# Controller_Board_-_Microcontroller.net
KiCad netlist of a schematic drawn in Altium Designer
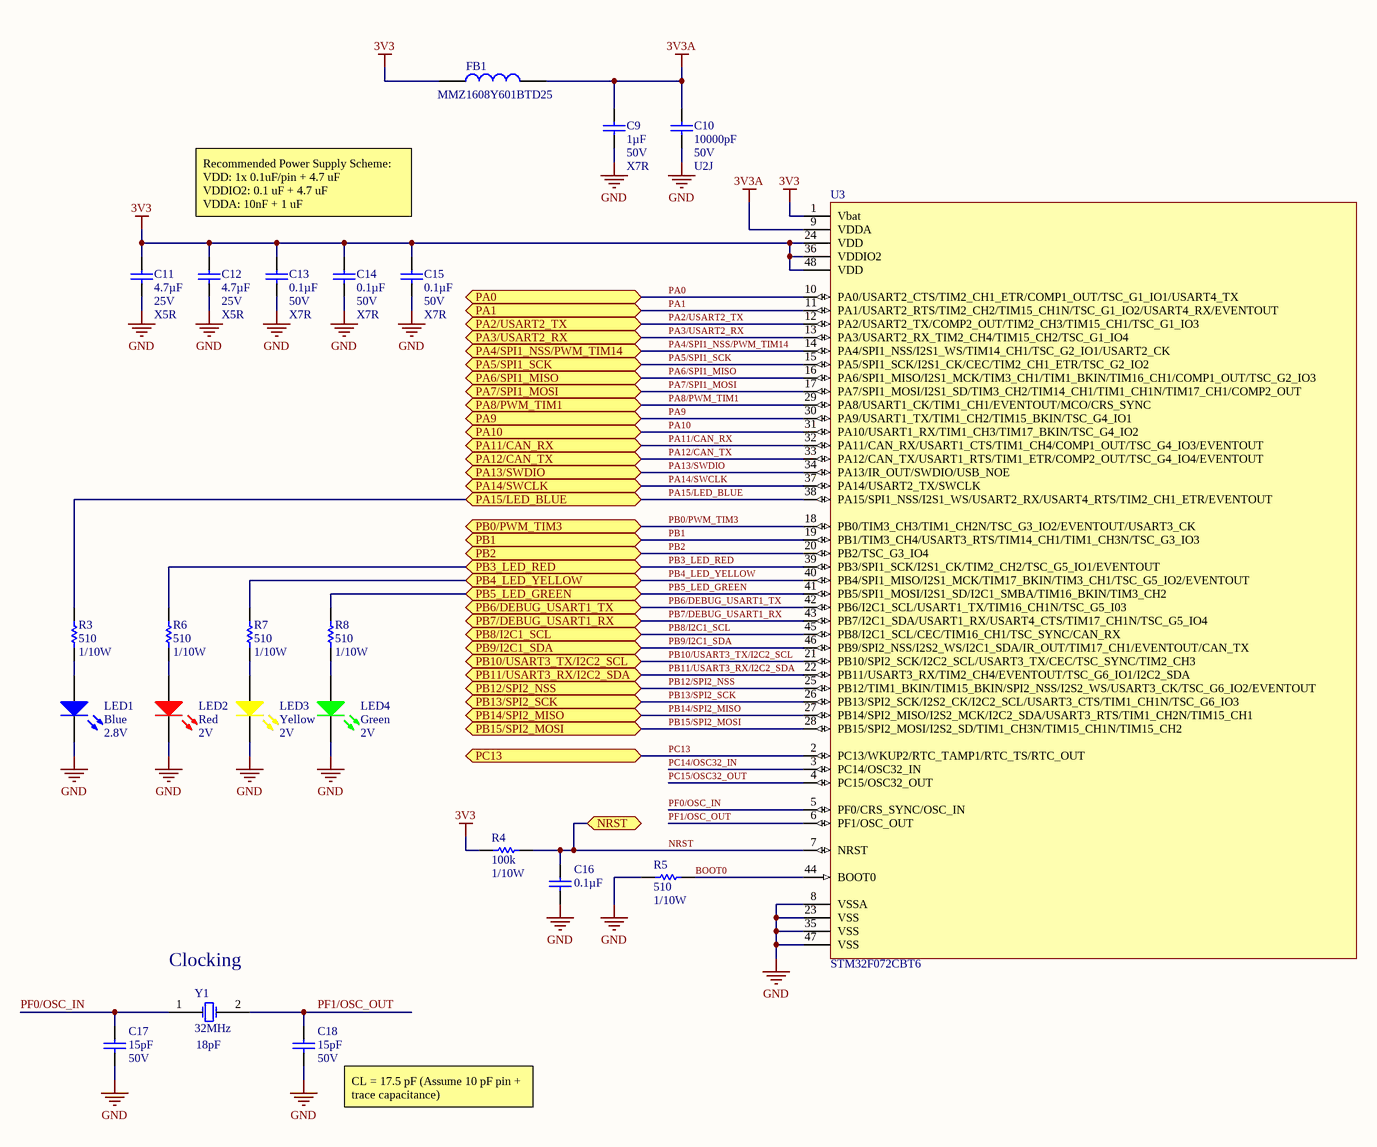
[diagram p0: Controller Board - Microcontroller.SchDoc]

(export (version "E")
  (design (tool "Eeschema 10.0.6"))
  (components
    (comp (ref "C9")
      (value "CAP CER 1UF 50V 10% X7R 0603")
      (footprint "CAP, 0603")
      (description "1µF ±10% 50V Ceramic Capacitor X7R 0603 (1608 Metric)")
      (fields
        (field (name "TOLERANCE") "±10%")
        (field (name "CAPACITANCE") "1µF")
        (field (name "VOLTAGE") "50V")
        (field (name "TEMPERATURE COEFFICIENT") "X7R")
      )
      (libsource (lib "Schematic Diagrams") (part "CAP CER 1UF 50V 10% X7R 0603"))
    )
    (comp (ref "C10")
      (value "CAP CER 10nF 50V 5% X7R 0603")
      (footprint "CAP, 0603")
      (description "10000pF ±5% 50V Ceramic Capacitor U2J 0603 (1608 Metric)")
      (fields
        (field (name "TOLERANCE") "±5%")
        (field (name "CAPACITANCE") "10000pF")
        (field (name "VOLTAGE") "50V")
        (field (name "TEMPERATURE COEFFICIENT") "U2J")
      )
      (libsource (lib "Schematic Diagrams") (part "CAP CER 10nF 50V 5% X7R 0603"))
    )
    (comp (ref "C11")
      (value "CAP CER 4.7UF 25V 10% X5R 0603")
      (footprint "CAP, 0603")
      (description "4.7µF ±10% 25V Ceramic Capacitor X5R 0603 (1608 Metric)")
      (fields
        (field (name "TOLERANCE") "±10%")
        (field (name "CAPACITANCE") "4.7µF")
        (field (name "VOLTAGE") "25V")
        (field (name "TEMPERATURE COEFFICIENT") "X5R")
      )
      (libsource (lib "Schematic Diagrams") (part "CAP CER 4.7UF 25V 10% X5R 0603"))
    )
    (comp (ref "C12")
      (value "CAP CER 4.7UF 25V 10% X5R 0603")
      (footprint "CAP, 0603")
      (description "4.7µF ±10% 25V Ceramic Capacitor X5R 0603 (1608 Metric)")
      (fields
        (field (name "TOLERANCE") "±10%")
        (field (name "CAPACITANCE") "4.7µF")
        (field (name "VOLTAGE") "25V")
        (field (name "TEMPERATURE COEFFICIENT") "X5R")
      )
      (libsource (lib "Schematic Diagrams") (part "CAP CER 4.7UF 25V 10% X5R 0603"))
    )
    (comp (ref "C13")
      (value "CAP CER 0.1UF 50V 10% X7R 0603")
      (footprint "CAP, 0603")
      (description "0.10µF ±10% 50V Ceramic Capacitor X7R 0603 (1608 Metric)")
      (fields
        (field (name "TOLERANCE") "±10%")
        (field (name "CAPACITANCE") "0.1µF")
        (field (name "VOLTAGE") "50V")
        (field (name "TEMPERATURE COEFFICIENT") "X7R")
      )
      (libsource (lib "Schematic Diagrams") (part "CAP CER 0.1UF 50V 10% X7R 0603"))
    )
    (comp (ref "C14")
      (value "CAP CER 0.1UF 50V 10% X7R 0603")
      (footprint "CAP, 0603")
      (description "0.10µF ±10% 50V Ceramic Capacitor X7R 0603 (1608 Metric)")
      (fields
        (field (name "TOLERANCE") "±10%")
        (field (name "CAPACITANCE") "0.1µF")
        (field (name "VOLTAGE") "50V")
        (field (name "TEMPERATURE COEFFICIENT") "X7R")
      )
      (libsource (lib "Schematic Diagrams") (part "CAP CER 0.1UF 50V 10% X7R 0603"))
    )
    (comp (ref "C15")
      (value "CAP CER 0.1UF 50V 10% X7R 0603")
      (footprint "CAP, 0603")
      (description "0.10µF ±10% 50V Ceramic Capacitor X7R 0603 (1608 Metric)")
      (fields
        (field (name "TOLERANCE") "±10%")
        (field (name "CAPACITANCE") "0.1µF")
        (field (name "VOLTAGE") "50V")
        (field (name "TEMPERATURE COEFFICIENT") "X7R")
      )
      (libsource (lib "Schematic Diagrams") (part "CAP CER 0.1UF 50V 10% X7R 0603"))
    )
    (comp (ref "C16")
      (value "CAP CER 0.1UF 50V 10% X7R 0603")
      (footprint "CAP, 0603")
      (description "0.10µF ±10% 50V Ceramic Capacitor X7R 0603 (1608 Metric)")
      (fields
        (field (name "VOLTAGE") "50V")
        (field (name "TOLERANCE") "±10%")
        (field (name "CAPACITANCE") "0.1µF")
      )
      (libsource (lib "Schematic Diagrams") (part "CAP CER 0.1UF 50V 10% X7R 0603"))
    )
    (comp (ref "C17")
      (value "CAP CER 15PF 50V ±5% NPO 0603")
      (footprint "CAP, 0603")
      (description "15pF ±5% 50V Ceramic Capacitor C0G, NP0 0603 (1608 Metric)")
      (fields
        (field (name "VOLTAGE") "50V")
        (field (name "TOLERANCE") "±5%")
        (field (name "CAPACITANCE") "15pF")
      )
      (libsource (lib "Schematic Diagrams") (part "CAP CER 15PF 50V ±5% NPO 0603"))
    )
    (comp (ref "C18")
      (value "CAP CER 15PF 50V ±5% NPO 0603")
      (footprint "CAP, 0603")
      (description "15pF ±5% 50V Ceramic Capacitor C0G, NP0 0603 (1608 Metric)")
      (fields
        (field (name "VOLTAGE") "50V")
        (field (name "TOLERANCE") "±5%")
        (field (name "CAPACITANCE") "15pF")
      )
      (libsource (lib "Schematic Diagrams") (part "CAP CER 15PF 50V ±5% NPO 0603"))
    )
    (comp (ref "FB1")
      (value "FB 600 OHM 1LN 0603")
      (footprint "FB 0603")
      (description "FERRITE BEAD 600 OHM 0603 1LN")
      (fields
        (field (name "MANUFACTURER") "TDK")
        (field (name "TOLERANCE") "25%")
        (field (name "MANUFACTURER PART NUMBER") "MMZ1608Y601BTD25")
      )
      (libsource (lib "Schematic Diagrams") (part "FB 600 OHM 1LN 0603"))
    )
    (comp (ref "LED1")
      (value "LED BLUE CLEAR 2.8V 0603")
      (footprint "LED_0603")
      (description "Blue 470nm LED Indication - Discrete 2.8V 0603 (1608 Metric)")
      (fields (field (name "COLOR") "Blue") (field (name "VOLTAGE - FORWARD (VF) (TYP)") "2.8V"))
      (libsource (lib "Schematic Diagrams") (part "LED BLUE CLEAR 2.8V 0603"))
    )
    (comp (ref "LED2")
      (value "LED RED CLEAR 2V 0603")
      (footprint "LED_0603")
      (description "Red 631nm LED Indication - Discrete 2V 0603 (1608 Metric)")
      (fields
        (field (name "MANUFACTURER") "Wurth Electronics Inc.")
        (field (name "MANUFACTURER PART NUMBER") "150060RS75000")
        (field (name "COLOR") "Red")
        (field (name "VOLTAGE - FORWARD (VF) (TYP)") "2V")
      )
      (libsource (lib "Schematic Diagrams") (part "LED RED CLEAR 2V 0603"))
    )
    (comp (ref "LED3")
      (value "LED YELLOW CLEAR 2.1V 0603")
      (footprint "LED_0603")
      (description "Yellow 590nm LED Indication - Discrete 2V 0603 (1608 Metric)")
      (fields
        (field (name "MANUFACTURER") "Wurth Electronics Inc.")
        (field (name "MANUFACTURER PART NUMBER") "150060YS75000")
        (field (name "COLOR") "Yellow")
        (field (name "VOLTAGE - FORWARD (VF) (TYP)") "2V")
      )
      (libsource (lib "Schematic Diagrams") (part "LED YELLOW CLEAR 2.1V 0603"))
    )
    (comp (ref "LED4")
      (value "LED GREEN CLEAR 2V 0603")
      (footprint "LED_0603")
      (description "Green 572nm LED Indication - Discrete 2V 0603 (1608 Metric)")
      (fields
        (field (name "MANUFACTURER") "Wurth Electronics Inc.")
        (field (name "MANUFACTURER PART NUMBER") "150060VS75000")
        (field (name "COLOR") "Green")
        (field (name "VOLTAGE - FORWARD (VF) (TYP)") "2V")
      )
      (libsource (lib "Schematic Diagrams") (part "LED GREEN CLEAR 2V 0603"))
    )
    (comp (ref "R3")
      (value "RES 510 OHM 5% 1/10W 0603")
      (footprint "RES, 0603")
      (description "RES SMD 510 OHM 5% 1/10W 0603")
      (fields
        (field (name "TOLERANCE") "±5%")
        (field (name "RESISTANCE") "510")
        (field (name "POWER") "1/10W")
      )
      (libsource (lib "altium-import") (part "root_0_RES 510 OHM 5% 1/10W 0603_"))
    )
    (comp (ref "R4")
      (value "RES 100K OHM 5% 1/8W 0603")
      (footprint "RES, 0603")
      (description "RES SMD 100K OHM 5% 1/10W 0603")
      (fields
        (field (name "TOLERANCE") "±5%")
        (field (name "RESISTANCE") "100k")
        (field (name "POWER") "1/10W")
      )
      (libsource (lib "Schematic Diagrams") (part "RES 100K OHM 5% 1/8W 0603"))
    )
    (comp (ref "R5")
      (value "RES 510 OHM 5% 1/10W 0603")
      (footprint "RES, 0603")
      (description "RES SMD 510 OHM 5% 1/10W 0603")
      (fields
        (field (name "TOLERANCE") "±5%")
        (field (name "RESISTANCE") "510")
        (field (name "POWER") "1/10W")
      )
      (libsource (lib "Schematic Diagrams") (part "RES 510 OHM 5% 1/10W 0603"))
    )
    (comp (ref "R6")
      (value "RES 510 OHM 5% 1/10W 0603")
      (footprint "RES, 0603")
      (description "RES SMD 510 OHM 5% 1/10W 0603")
      (fields
        (field (name "TOLERANCE") "±5%")
        (field (name "RESISTANCE") "510")
        (field (name "POWER") "1/10W")
      )
      (libsource (lib "altium-import") (part "root_0_RES 510 OHM 5% 1/10W 0603_"))
    )
    (comp (ref "R7")
      (value "RES 510 OHM 5% 1/10W 0603")
      (footprint "RES, 0603")
      (description "RES SMD 510 OHM 5% 1/10W 0603")
      (fields
        (field (name "TOLERANCE") "±5%")
        (field (name "RESISTANCE") "510")
        (field (name "POWER") "1/10W")
      )
      (libsource (lib "altium-import") (part "root_0_RES 510 OHM 5% 1/10W 0603_"))
    )
    (comp (ref "R8")
      (value "RES 510 OHM 5% 1/10W 0603")
      (footprint "RES, 0603")
      (description "RES SMD 510 OHM 5% 1/10W 0603")
      (fields
        (field (name "TOLERANCE") "±5%")
        (field (name "RESISTANCE") "510")
        (field (name "POWER") "1/10W")
      )
      (libsource (lib "altium-import") (part "root_0_RES 510 OHM 5% 1/10W 0603_"))
    )
    (comp (ref "U3")
      (value "IC MCU 32BIT 128KB FLASH 48LQFP")
      (footprint "TSQFP50P890X890X160-48M")
      (description "ARM® Cortex®-M0 STM32 F0 Microcontroller IC 32-Bit 48MHz 128KB (128K x 8) FLASH 48-LQFP (7x7)")
      (fields (field (name "MANUFACTURER PART NUMBER 1") "STM32F072CBT6"))
      (libsource (lib "Schematic Diagrams") (part "IC MCU 32BIT 128KB FLASH 48LQFP"))
    )
    (comp (ref "Y1")
      (value "CRYSTAL 32 MHz 18PF 2-SMD")
      (footprint "CRYSTAL ABM7")
      (description "32MHz ±20ppm Crystal 18pF 50 Ohms 2-SMD, No Lead")
      (fields
        (field (name "MANUFACTURER") "Abracon")
        (field (name "LOAD CAPACITANCE") "18pF")
        (field (name "TOLERANCE") "20ppm")
        (field (name "FREQUENCY") "32MHz")
      )
      (libsource (lib "Schematic Diagrams") (part "CRYSTAL 32 MHz 18PF 2-SMD"))
    )
  )
  (nets
    (net (code "1") (name "/BOOT0") (class "Default")
      (node (ref "R5") (pin "2") (pinfunction "2_2") (pintype "passive"))
      (node (ref "U3") (pin "44") (pinfunction "BOOT0_44") (pintype "input"))
    )
    (net (code "2") (name "/NRST") (class "Default")
      (node (ref "C16") (pin "2") (pinfunction "2_2") (pintype "passive"))
      (node (ref "R4") (pin "1") (pinfunction "1_1") (pintype "passive"))
      (node (ref "U3") (pin "7") (pinfunction "NRST_7") (pintype "bidirectional"))
    )
    (net (code "3") (name "/PA0") (class "Default")
      (node (ref "U3") (pin "10") (pinfunction "PA0/USART2_CTS/TIM2_CH1_ETR/COMP1_OUT/TSC_G1_IO1/USART4_TX_10") (pintype "bidirectional"))
    )
    (net (code "4") (name "/PA1") (class "Default")
      (node (ref "U3") (pin "11") (pinfunction "PA1/USART2_RTS/TIM2_CH2/TIM15_CH1N/TSC_G1_IO2/USART4_RX/EVENTOUT_11") (pintype "bidirectional"))
    )
    (net (code "5") (name "/PA2{slash}USART2_TX") (class "Default")
      (node (ref "U3") (pin "12") (pinfunction "PA2/USART2_TX/COMP2_OUT/TIM2_CH3/TIM15_CH1/TSC_G1_IO3_12") (pintype "bidirectional"))
    )
    (net (code "6") (name "/PA3{slash}USART2_RX") (class "Default")
      (node (ref "U3") (pin "13") (pinfunction "PA3/USART2_RX_TIM2_CH4/TIM15_CH2/TSC_G1_IO4_13") (pintype "bidirectional"))
    )
    (net (code "7") (name "/PA4{slash}SPI1_NSS{slash}PWM_TIM14") (class "Default")
      (node (ref "U3") (pin "14") (pinfunction "PA4/SPI1_NSS/I2S1_WS/TIM14_CH1/TSC_G2_IO1/USART2_CK_14") (pintype "bidirectional"))
    )
    (net (code "8") (name "/PA5{slash}SPI1_SCK") (class "Default")
      (node (ref "U3") (pin "15") (pinfunction "PA5/SPI1_SCK/I2S1_CK/CEC/TIM2_CH1_ETR/TSC_G2_IO2_15") (pintype "bidirectional"))
    )
    (net (code "9") (name "/PA6{slash}SPI1_MISO") (class "Default")
      (node (ref "U3") (pin "16") (pinfunction "PA6/SPI1_MISO/I2S1_MCK/TIM3_CH1/TIM1_BKIN/TIM16_CH1/COMP1_OUT/TSC_G2_IO3_16") (pintype "bidirectional"))
    )
    (net (code "10") (name "/PA7{slash}SPI1_MOSI") (class "Default")
      (node (ref "U3") (pin "17") (pinfunction "PA7/SPI1_MOSI/I2S1_SD/TIM3_CH2/TIM14_CH1/TIM1_CH1N/TIM17_CH1/COMP2_OUT_17") (pintype "bidirectional"))
    )
    (net (code "11") (name "/PA8{slash}PWM_TIM1") (class "Default")
      (node (ref "U3") (pin "29") (pinfunction "PA8/USART1_CK/TIM1_CH1/EVENTOUT/MCO/CRS_SYNC_29") (pintype "bidirectional"))
    )
    (net (code "12") (name "/PA9") (class "Default")
      (node (ref "U3") (pin "30") (pinfunction "PA9/USART1_TX/TIM1_CH2/TIM15_BKIN/TSC_G4_IO1_30") (pintype "bidirectional"))
    )
    (net (code "13") (name "/PA10") (class "Default")
      (node (ref "U3") (pin "31") (pinfunction "PA10/USART1_RX/TIM1_CH3/TIM17_BKIN/TSC_G4_IO2_31") (pintype "bidirectional"))
    )
    (net (code "14") (name "/PA11{slash}CAN_RX") (class "Default")
      (node (ref "U3") (pin "32") (pinfunction "PA11/CAN_RX/USART1_CTS/TIM1_CH4/COMP1_OUT/TSC_G4_IO3/EVENTOUT_32") (pintype "bidirectional"))
    )
    (net (code "15") (name "/PA12{slash}CAN_TX") (class "Default")
      (node (ref "U3") (pin "33") (pinfunction "PA12/CAN_TX/USART1_RTS/TIM1_ETR/COMP2_OUT/TSC_G4_IO4/EVENTOUT_33") (pintype "bidirectional"))
    )
    (net (code "16") (name "/PA13{slash}SWDIO") (class "Default")
      (node (ref "U3") (pin "34") (pinfunction "PA13/IR_OUT/SWDIO/USB_NOE_34") (pintype "bidirectional"))
    )
    (net (code "17") (name "/PA14{slash}SWCLK") (class "Default")
      (node (ref "U3") (pin "37") (pinfunction "PA14/USART2_TX/SWCLK_37") (pintype "bidirectional"))
    )
    (net (code "18") (name "/PA15{slash}LED_BLUE") (class "Default")
      (node (ref "R3") (pin "1") (pinfunction "1_1") (pintype "passive"))
      (node (ref "U3") (pin "38") (pinfunction "PA15/SPI1_NSS/I2S1_WS/USART2_RX/USART4_RTS/TIM2_CH1_ETR/EVENTOUT_38") (pintype "bidirectional"))
    )
    (net (code "19") (name "/PB0{slash}PWM_TIM3") (class "Default")
      (node (ref "U3") (pin "18") (pinfunction "PB0/TIM3_CH3/TIM1_CH2N/TSC_G3_IO2/EVENTOUT/USART3_CK_18") (pintype "bidirectional"))
    )
    (net (code "20") (name "/PB1") (class "Default")
      (node (ref "U3") (pin "19") (pinfunction "PB1/TIM3_CH4/USART3_RTS/TIM14_CH1/TIM1_CH3N/TSC_G3_IO3_19") (pintype "bidirectional"))
    )
    (net (code "21") (name "/PB2") (class "Default")
      (node (ref "U3") (pin "20") (pinfunction "PB2/TSC_G3_IO4_20") (pintype "bidirectional"))
    )
    (net (code "22") (name "/PB3_LED_RED") (class "Default")
      (node (ref "R6") (pin "1") (pinfunction "1_1") (pintype "passive"))
      (node (ref "U3") (pin "39") (pinfunction "PB3/SPI1_SCK/I2S1_CK/TIM2_CH2/TSC_G5_IO1/EVENTOUT_39") (pintype "bidirectional"))
    )
    (net (code "23") (name "/PB4_LED_YELLOW") (class "Default")
      (node (ref "R7") (pin "1") (pinfunction "1_1") (pintype "passive"))
      (node (ref "U3") (pin "40") (pinfunction "PB4/SPI1_MISO/I2S1_MCK/TIM17_BKIN/TIM3_CH1/TSC_G5_IO2/EVENTOUT_40") (pintype "bidirectional"))
    )
    (net (code "24") (name "/PB5_LED_GREEN") (class "Default")
      (node (ref "R8") (pin "1") (pinfunction "1_1") (pintype "passive"))
      (node (ref "U3") (pin "41") (pinfunction "PB5/SPI1_MOSI/I2S1_SD/I2C1_SMBA/TIM16_BKIN/TIM3_CH2_41") (pintype "bidirectional"))
    )
    (net (code "25") (name "/PB6{slash}DEBUG_USART1_TX") (class "Default")
      (node (ref "U3") (pin "42") (pinfunction "PB6/I2C1_SCL/USART1_TX/TIM16_CH1N/TSC_G5_I03_42") (pintype "bidirectional"))
    )
    (net (code "26") (name "/PB7{slash}DEBUG_USART1_RX") (class "Default")
      (node (ref "U3") (pin "43") (pinfunction "PB7/I2C1_SDA/USART1_RX/USART4_CTS/TIM17_CH1N/TSC_G5_IO4_43") (pintype "bidirectional"))
    )
    (net (code "27") (name "/PB8{slash}I2C1_SCL") (class "Default")
      (node (ref "U3") (pin "45") (pinfunction "PB8/I2C1_SCL/CEC/TIM16_CH1/TSC_SYNC/CAN_RX_45") (pintype "bidirectional"))
    )
    (net (code "28") (name "/PB9{slash}I2C1_SDA") (class "Default")
      (node (ref "U3") (pin "46") (pinfunction "PB9/SPI2_NSS/I2S2_WS/I2C1_SDA/IR_OUT/TIM17_CH1/EVENTOUT/CAN_TX_46") (pintype "bidirectional"))
    )
    (net (code "29") (name "/PB10{slash}USART3_TX{slash}I2C2_SCL") (class "Default")
      (node (ref "U3") (pin "21") (pinfunction "PB10/SPI2_SCK/I2C2_SCL/USART3_TX/CEC/TSC_SYNC/TIM2_CH3_21") (pintype "bidirectional"))
    )
    (net (code "30") (name "/PB11{slash}USART3_RX{slash}I2C2_SDA") (class "Default")
      (node (ref "U3") (pin "22") (pinfunction "PB11/USART3_RX/TIM2_CH4/EVENTOUT/TSC_G6_IO1/I2C2_SDA_22") (pintype "bidirectional"))
    )
    (net (code "31") (name "/PB12{slash}SPI2_NSS") (class "Default")
      (node (ref "U3") (pin "25") (pinfunction "PB12/TIM1_BKIN/TIM15_BKIN/SPI2_NSS/I2S2_WS/USART3_CK/TSC_G6_IO2/EVENTOUT_25") (pintype "bidirectional"))
    )
    (net (code "32") (name "/PB13{slash}SPI2_SCK") (class "Default")
      (node (ref "U3") (pin "26") (pinfunction "PB13/SPI2_SCK/I2S2_CK/I2C2_SCL/USART3_CTS/TIM1_CH1N/TSC_G6_IO3_26") (pintype "bidirectional"))
    )
    (net (code "33") (name "/PB14{slash}SPI2_MISO") (class "Default")
      (node (ref "U3") (pin "27") (pinfunction "PB14/SPI2_MISO/I2S2_MCK/I2C2_SDA/USART3_RTS/TIM1_CH2N/TIM15_CH1_27") (pintype "bidirectional"))
    )
    (net (code "34") (name "/PB15{slash}SPI2_MOSI") (class "Default")
      (node (ref "U3") (pin "28") (pinfunction "PB15/SPI2_MOSI/I2S2_SD/TIM1_CH3N/TIM15_CH1N/TIM15_CH2_28") (pintype "bidirectional"))
    )
    (net (code "35") (name "/PC13") (class "Default")
      (node (ref "U3") (pin "2") (pinfunction "PC13/WKUP2/RTC_TAMP1/RTC_TS/RTC_OUT_2") (pintype "bidirectional"))
    )
    (net (code "36") (name "/PC14{slash}OSC32_IN") (class "Default")
      (node (ref "U3") (pin "3") (pinfunction "PC14/OSC32_IN_3") (pintype "bidirectional"))
    )
    (net (code "37") (name "/PC15{slash}OSC32_OUT") (class "Default")
      (node (ref "U3") (pin "4") (pinfunction "PC15/OSC32_OUT_4") (pintype "bidirectional"))
    )
    (net (code "38") (name "/PF0{slash}OSC_IN") (class "Default")
      (node (ref "C17") (pin "2") (pinfunction "2_2") (pintype "passive"))
      (node (ref "U3") (pin "5") (pinfunction "PF0/CRS_SYNC/OSC_IN_5") (pintype "bidirectional"))
      (node (ref "Y1") (pin "1") (pinfunction "1_1") (pintype "passive"))
    )
    (net (code "39") (name "/PF1{slash}OSC_OUT") (class "Default")
      (node (ref "C18") (pin "2") (pinfunction "2_2") (pintype "passive"))
      (node (ref "U3") (pin "6") (pinfunction "PF1/OSC_OUT_6") (pintype "bidirectional"))
      (node (ref "Y1") (pin "2") (pinfunction "2_2") (pintype "passive"))
    )
    (net (code "40") (name "3V3") (class "Default")
      (node (ref "C11") (pin "1") (pinfunction "1_1") (pintype "passive"))
      (node (ref "C12") (pin "1") (pinfunction "1_1") (pintype "passive"))
      (node (ref "C13") (pin "1") (pinfunction "1_1") (pintype "passive"))
      (node (ref "C14") (pin "1") (pinfunction "1_1") (pintype "passive"))
      (node (ref "C15") (pin "1") (pinfunction "1_1") (pintype "passive"))
      (node (ref "FB1") (pin "1") (pinfunction "1_1") (pintype "passive"))
      (node (ref "R4") (pin "2") (pinfunction "2_2") (pintype "passive"))
      (node (ref "U3") (pin "1") (pinfunction "Vbat_1") (pintype "power_in"))
      (node (ref "U3") (pin "24") (pinfunction "VDD_24") (pintype "power_in"))
      (node (ref "U3") (pin "36") (pinfunction "VDDIO2_36") (pintype "power_in"))
      (node (ref "U3") (pin "48") (pinfunction "VDD_48") (pintype "power_in"))
    )
    (net (code "41") (name "3V3A") (class "Default")
      (node (ref "C10") (pin "1") (pinfunction "1_1") (pintype "passive"))
      (node (ref "C9") (pin "1") (pinfunction "1_1") (pintype "passive"))
      (node (ref "FB1") (pin "2") (pinfunction "2_2") (pintype "passive"))
      (node (ref "U3") (pin "9") (pinfunction "VDDA_9") (pintype "power_in"))
    )
    (net (code "42") (name "GND") (class "Default")
      (node (ref "C10") (pin "2") (pinfunction "2_2") (pintype "passive"))
      (node (ref "C11") (pin "2") (pinfunction "2_2") (pintype "passive"))
      (node (ref "C12") (pin "2") (pinfunction "2_2") (pintype "passive"))
      (node (ref "C13") (pin "2") (pinfunction "2_2") (pintype "passive"))
      (node (ref "C14") (pin "2") (pinfunction "2_2") (pintype "passive"))
      (node (ref "C15") (pin "2") (pinfunction "2_2") (pintype "passive"))
      (node (ref "C16") (pin "1") (pinfunction "1_1") (pintype "passive"))
      (node (ref "C17") (pin "1") (pinfunction "1_1") (pintype "passive"))
      (node (ref "C18") (pin "1") (pinfunction "1_1") (pintype "passive"))
      (node (ref "C9") (pin "2") (pinfunction "2_2") (pintype "passive"))
      (node (ref "LED1") (pin "2") (pinfunction "K_2") (pintype "passive"))
      (node (ref "LED2") (pin "2") (pinfunction "K_2") (pintype "passive"))
      (node (ref "LED3") (pin "2") (pinfunction "K_2") (pintype "passive"))
      (node (ref "LED4") (pin "2") (pinfunction "K_2") (pintype "passive"))
      (node (ref "R5") (pin "1") (pinfunction "1_1") (pintype "passive"))
      (node (ref "U3") (pin "23") (pinfunction "VSS_23") (pintype "power_in"))
      (node (ref "U3") (pin "35") (pinfunction "VSS_35") (pintype "power_in"))
      (node (ref "U3") (pin "47") (pinfunction "VSS_47") (pintype "power_in"))
      (node (ref "U3") (pin "8") (pinfunction "VSSA_8") (pintype "power_in"))
    )
    (net (code "43") (name "Net-(LED1-A)") (class "Default")
      (node (ref "LED1") (pin "1") (pinfunction "A_1") (pintype "passive"))
      (node (ref "R3") (pin "2") (pinfunction "2_2") (pintype "passive"))
    )
    (net (code "44") (name "Net-(LED2-A)") (class "Default")
      (node (ref "LED2") (pin "1") (pinfunction "A_1") (pintype "passive"))
      (node (ref "R6") (pin "2") (pinfunction "2_2") (pintype "passive"))
    )
    (net (code "45") (name "Net-(LED3-A)") (class "Default")
      (node (ref "LED3") (pin "1") (pinfunction "A_1") (pintype "passive"))
      (node (ref "R7") (pin "2") (pinfunction "2_2") (pintype "passive"))
    )
    (net (code "46") (name "Net-(LED4-A)") (class "Default")
      (node (ref "LED4") (pin "1") (pinfunction "A_1") (pintype "passive"))
      (node (ref "R8") (pin "2") (pinfunction "2_2") (pintype "passive"))
    )
  )
)
